# L3DCube_X16_Daughterboard_Rev3.net
KiCad netlist of a schematic drawn in EAGLE
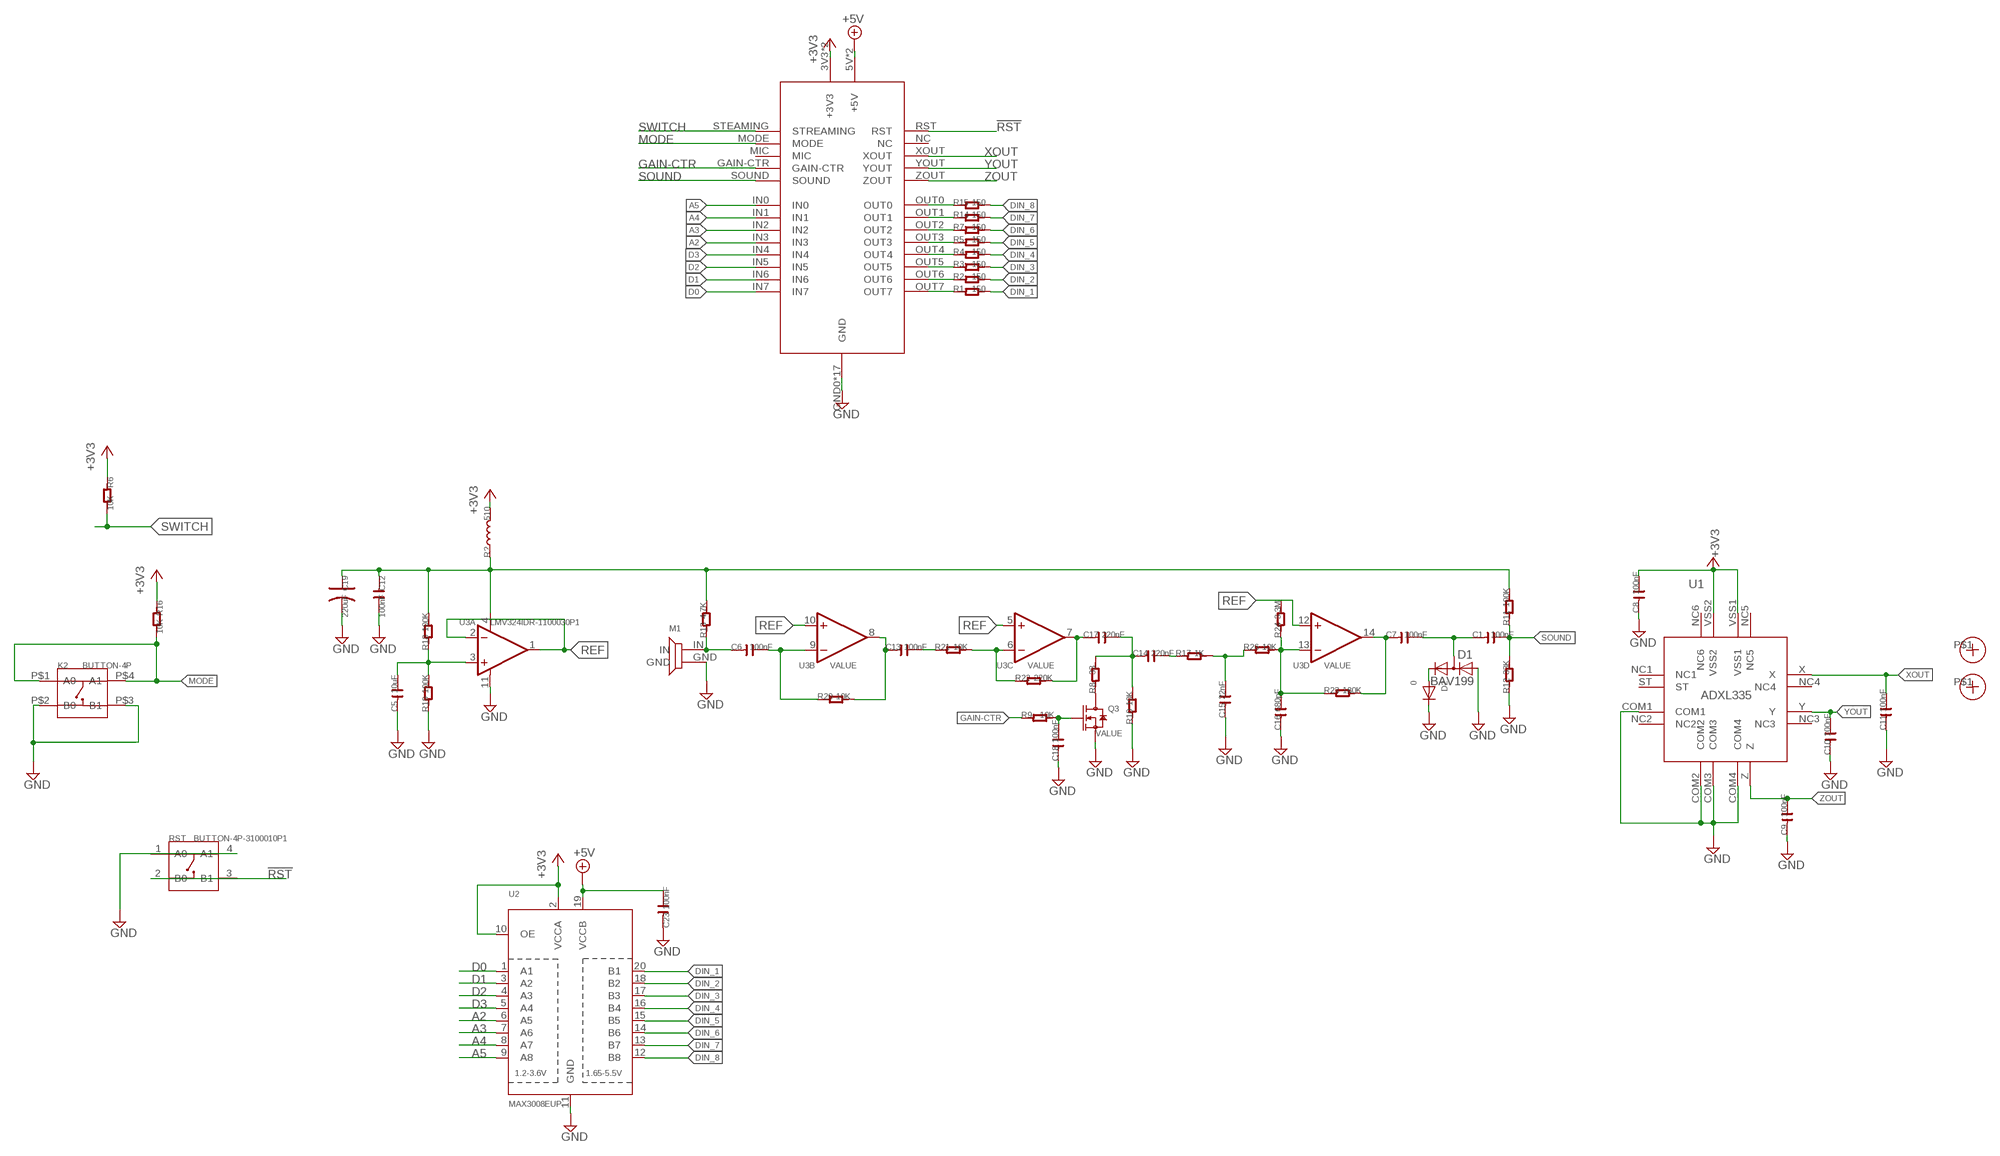
[diagram p0: schematic, sheet 1]

(export (version "E")
  (design (tool "Eeschema 10.0.6"))
  (components
    (comp (ref "C1")
      (value "100nF")
      (footprint "eagle-import:C0603")
      (libsource (lib "eagle-import") (part "C-0603"))
    )
    (comp (ref "C5")
      (value "10uF")
      (footprint "eagle-import:C0603")
      (libsource (lib "eagle-import") (part "C-0603"))
    )
    (comp (ref "C6")
      (value "100nF")
      (footprint "eagle-import:C0603")
      (libsource (lib "eagle-import") (part "C-0603"))
    )
    (comp (ref "C7")
      (value "100nF")
      (footprint "eagle-import:C0603")
      (libsource (lib "eagle-import") (part "C-0603"))
    )
    (comp (ref "C8")
      (value "100nF")
      (footprint "eagle-import:C0603")
      (libsource (lib "eagle-import") (part "C-0603"))
    )
    (comp (ref "C9")
      (value "100nF")
      (footprint "eagle-import:C0603")
      (libsource (lib "eagle-import") (part "C-0603"))
    )
    (comp (ref "C10")
      (value "100nF")
      (footprint "eagle-import:C0603")
      (libsource (lib "eagle-import") (part "C-0603"))
    )
    (comp (ref "C11")
      (value "100nF")
      (footprint "eagle-import:C0603")
      (libsource (lib "eagle-import") (part "C-0603"))
    )
    (comp (ref "C12")
      (value "100nF")
      (footprint "eagle-import:C0603")
      (libsource (lib "eagle-import") (part "C-0603"))
    )
    (comp (ref "C13")
      (value "100nF")
      (footprint "eagle-import:C0603")
      (libsource (lib "eagle-import") (part "C-0603"))
    )
    (comp (ref "C14")
      (value "220nF")
      (footprint "eagle-import:C0603")
      (libsource (lib "eagle-import") (part "C-0603"))
    )
    (comp (ref "C15")
      (value "22nF")
      (footprint "eagle-import:C0603")
      (libsource (lib "eagle-import") (part "C-0603"))
    )
    (comp (ref "C16")
      (value "680pF")
      (footprint "eagle-import:C0603")
      (libsource (lib "eagle-import") (part "C-0603"))
    )
    (comp (ref "C17")
      (value "220nF")
      (footprint "eagle-import:C0603")
      (libsource (lib "eagle-import") (part "C-0603"))
    )
    (comp (ref "C18")
      (value "100nF")
      (footprint "eagle-import:C0603")
      (libsource (lib "eagle-import") (part "C-0603"))
    )
    (comp (ref "C19")
      (value "220uF")
      (footprint "eagle-import:AVX-B")
      (libsource (lib "eagle-import") (part "C-POLAR-B"))
    )
    (comp (ref "C23")
      (value "100nF")
      (footprint "eagle-import:C0603")
      (libsource (lib "eagle-import") (part "C-0603"))
    )
    (comp (ref "D1")
      (value "BAV199")
      (footprint "eagle-import:SOT23")
      (libsource (lib "eagle-import") (part "BAV199"))
    )
    (comp (ref "D2")
      (value "0")
      (footprint "eagle-import:SOD-123")
      (libsource (lib "eagle-import") (part "DIODESOD-123"))
    )
    (comp (ref "K2")
      (value "BUTTON-4P")
      (footprint "eagle-import:4P-12X12X6-SMD")
      (libsource (lib "eagle-import") (part "BUTTON-4P"))
    )
    (comp (ref "M1")
      (value "MICROPHONE")
      (footprint "eagle-import:MICROPHONE")
      (libsource (lib "eagle-import") (part "MICROPHONE"))
    )
    (comp (ref "Q3")
      (value "2N7002")
      (footprint "eagle-import:SOT23")
      (libsource (lib "eagle-import") (part "MOSFET-N-044020001"))
    )
    (comp (ref "R1")
      (value "150")
      (footprint "eagle-import:R0603")
      (libsource (lib "eagle-import") (part "R-0603"))
    )
    (comp (ref "R2")
      (value "150")
      (footprint "eagle-import:R0603")
      (libsource (lib "eagle-import") (part "R-0603"))
    )
    (comp (ref "R3")
      (value "150")
      (footprint "eagle-import:R0603")
      (libsource (lib "eagle-import") (part "R-0603"))
    )
    (comp (ref "R4")
      (value "150")
      (footprint "eagle-import:R0603")
      (libsource (lib "eagle-import") (part "R-0603"))
    )
    (comp (ref "R5")
      (value "150")
      (footprint "eagle-import:R0603")
      (libsource (lib "eagle-import") (part "R-0603"))
    )
    (comp (ref "R6")
      (value "10K")
      (footprint "eagle-import:R0603")
      (libsource (lib "eagle-import") (part "R-0603"))
    )
    (comp (ref "R7")
      (value "150")
      (footprint "eagle-import:R0603")
      (libsource (lib "eagle-import") (part "R-0603"))
    )
    (comp (ref "R8")
      (value "33")
      (footprint "eagle-import:R0603")
      (libsource (lib "eagle-import") (part "R-0603"))
    )
    (comp (ref "R9")
      (value "10K")
      (footprint "eagle-import:R0603")
      (libsource (lib "eagle-import") (part "R-0603"))
    )
    (comp (ref "R10")
      (value "10K")
      (footprint "eagle-import:R0603")
      (libsource (lib "eagle-import") (part "R-0603"))
    )
    (comp (ref "R11")
      (value "100K")
      (footprint "eagle-import:R0603")
      (libsource (lib "eagle-import") (part "R-0603"))
    )
    (comp (ref "R12")
      (value "33K")
      (footprint "eagle-import:R0603")
      (libsource (lib "eagle-import") (part "R-0603"))
    )
    (comp (ref "R13")
      (value "4.7K")
      (footprint "eagle-import:R0603")
      (libsource (lib "eagle-import") (part "R-0603"))
    )
    (comp (ref "R14")
      (value "150")
      (footprint "eagle-import:R0603")
      (libsource (lib "eagle-import") (part "R-0603"))
    )
    (comp (ref "R15")
      (value "150")
      (footprint "eagle-import:R0603")
      (libsource (lib "eagle-import") (part "R-0603"))
    )
    (comp (ref "R16")
      (value "10K")
      (footprint "eagle-import:R0603")
      (libsource (lib "eagle-import") (part "R-0603"))
    )
    (comp (ref "R17")
      (value "1K")
      (footprint "eagle-import:R0603")
      (libsource (lib "eagle-import") (part "R-0603"))
    )
    (comp (ref "R18")
      (value "100K")
      (footprint "eagle-import:R0603")
      (libsource (lib "eagle-import") (part "R-0603"))
    )
    (comp (ref "R19")
      (value "100K")
      (footprint "eagle-import:R0603")
      (libsource (lib "eagle-import") (part "R-0603"))
    )
    (comp (ref "R20")
      (value "10K")
      (footprint "eagle-import:R0603")
      (libsource (lib "eagle-import") (part "R-0603"))
    )
    (comp (ref "R21")
      (value "10K")
      (footprint "eagle-import:R0603")
      (libsource (lib "eagle-import") (part "R-0603"))
    )
    (comp (ref "R22")
      (value "220K")
      (footprint "eagle-import:R0603")
      (libsource (lib "eagle-import") (part "R-0603"))
    )
    (comp (ref "R23")
      (value "180K")
      (footprint "eagle-import:R0603")
      (libsource (lib "eagle-import") (part "R-0603"))
    )
    (comp (ref "R24")
      (value "3.3M")
      (footprint "eagle-import:R0603")
      (libsource (lib "eagle-import") (part "R-0603"))
    )
    (comp (ref "R26")
      (value "10K")
      (footprint "eagle-import:R0603")
      (libsource (lib "eagle-import") (part "R-0603"))
    )
    (comp (ref "R?")
      (value "510")
      (footprint "eagle-import:L0603")
      (libsource (lib "eagle-import") (part "L-0603"))
    )
    (comp (ref "RST")
      (value "BUTTON-4P-3100010P1")
      (footprint "eagle-import:4P-SMD-6.0X6.0X5.0H")
      (libsource (lib "eagle-import") (part "BUTTON-4P-3100010P1"))
    )
    (comp (ref "U$1")
      (value "CUBE-16-DAUGHTERBOARD")
      (footprint "eagle-import:CUBE-16-DAUGHTERBOARD")
      (libsource (lib "eagle-import") (part "CUBE-16-DAUGHTERBOARD"))
    )
    (comp (ref "U$2")
      (value "FIDUCIAL-MARK")
      (footprint "eagle-import:FIDUCIAL-MARK")
      (libsource (lib "eagle-import") (part "FIDUCIAL-MARK"))
    )
    (comp (ref "U$3")
      (value "FIDUCIAL-MARK")
      (footprint "eagle-import:FIDUCIAL-MARK")
      (libsource (lib "eagle-import") (part "FIDUCIAL-MARK"))
    )
    (comp (ref "U1")
      (value "ADXL335")
      (footprint "eagle-import:ADXL335")
      (libsource (lib "eagle-import") (part "ADXL335"))
    )
    (comp (ref "U2")
      (value "MAX3008EUP")
      (footprint "eagle-import:TSSOP20")
      (libsource (lib "eagle-import") (part "TXB0108PWR"))
    )
    (comp (ref "U3")
      (value "LMV324IDR-1100030P1")
      (footprint "eagle-import:SOIC14")
      (libsource (lib "eagle-import") (part "LMV324IDR-1100030P1"))
    )
  )
  (nets
    (net (code "1") (name "+3V3") (class "Default")
      (node (ref "C8") (pin "2") (pinfunction "2_2") (pintype "bidirectional"))
      (node (ref "R16") (pin "1") (pinfunction "1_1") (pintype "bidirectional"))
      (node (ref "R6") (pin "1") (pinfunction "1_1") (pintype "bidirectional"))
      (node (ref "R?") (pin "2") (pinfunction "2_2") (pintype "passive"))
      (node (ref "U$1") (pin "3V3") (pinfunction "+3V3_3V3") (pintype "bidirectional"))
      (node (ref "U$1") (pin "3V3'") (pinfunction "+3V3_3V3'") (pintype "bidirectional"))
      (node (ref "U1") (pin "VSS1") (pinfunction "VSS1_VSS1") (pintype "bidirectional"))
      (node (ref "U1") (pin "VSS2") (pinfunction "VSS2_VSS2") (pintype "bidirectional"))
      (node (ref "U2") (pin "10") (pinfunction "OE_10") (pintype "bidirectional"))
      (node (ref "U2") (pin "2") (pinfunction "VCCA_2") (pintype "bidirectional"))
    )
    (net (code "2") (name "+5V") (class "Default")
      (node (ref "C23") (pin "2") (pinfunction "2_2") (pintype "bidirectional"))
      (node (ref "U$1") (pin "5V") (pinfunction "+5V_5V") (pintype "bidirectional"))
      (node (ref "U$1") (pin "5V'") (pinfunction "+5V_5V'") (pintype "bidirectional"))
      (node (ref "U2") (pin "19") (pinfunction "VCCB_19") (pintype "bidirectional"))
    )
    (net (code "3") (name "/~{RST}") (class "Default")
      (node (ref "RST") (pin "2") (pinfunction "B0_2") (pintype "bidirectional"))
      (node (ref "RST") (pin "3") (pinfunction "B1_3") (pintype "bidirectional"))
      (node (ref "U$1") (pin "RST") (pinfunction "RST_RST") (pintype "bidirectional"))
    )
    (net (code "4") (name "A2") (class "Default")
      (node (ref "U$1") (pin "IN3") (pinfunction "IN3_IN3") (pintype "bidirectional"))
      (node (ref "U2") (pin "6") (pinfunction "A5_6") (pintype "bidirectional"))
    )
    (net (code "5") (name "A3") (class "Default")
      (node (ref "U$1") (pin "IN2") (pinfunction "IN2_IN2") (pintype "bidirectional"))
      (node (ref "U2") (pin "7") (pinfunction "A6_7") (pintype "bidirectional"))
    )
    (net (code "6") (name "A4") (class "Default")
      (node (ref "U$1") (pin "IN1") (pinfunction "IN1_IN1") (pintype "bidirectional"))
      (node (ref "U2") (pin "8") (pinfunction "A7_8") (pintype "bidirectional"))
    )
    (net (code "7") (name "A5") (class "Default")
      (node (ref "U$1") (pin "IN0") (pinfunction "IN0_IN0") (pintype "bidirectional"))
      (node (ref "U2") (pin "9") (pinfunction "A8_9") (pintype "bidirectional"))
    )
    (net (code "8") (name "D0") (class "Default")
      (node (ref "U$1") (pin "IN7") (pinfunction "IN7_IN7") (pintype "bidirectional"))
      (node (ref "U2") (pin "1") (pinfunction "A1_1") (pintype "bidirectional"))
    )
    (net (code "9") (name "D1") (class "Default")
      (node (ref "U$1") (pin "IN6") (pinfunction "IN6_IN6") (pintype "bidirectional"))
      (node (ref "U2") (pin "3") (pinfunction "A2_3") (pintype "bidirectional"))
    )
    (net (code "10") (name "D2") (class "Default")
      (node (ref "U$1") (pin "IN5") (pinfunction "IN5_IN5") (pintype "bidirectional"))
      (node (ref "U2") (pin "4") (pinfunction "A3_4") (pintype "bidirectional"))
    )
    (net (code "11") (name "D3") (class "Default")
      (node (ref "U$1") (pin "IN4") (pinfunction "IN4_IN4") (pintype "bidirectional"))
      (node (ref "U2") (pin "5") (pinfunction "A4_5") (pintype "bidirectional"))
    )
    (net (code "12") (name "DIN_1") (class "Default")
      (node (ref "R1") (pin "2") (pinfunction "2_2") (pintype "bidirectional"))
      (node (ref "U2") (pin "20") (pinfunction "B1_20") (pintype "bidirectional"))
    )
    (net (code "13") (name "DIN_2") (class "Default")
      (node (ref "R2") (pin "2") (pinfunction "2_2") (pintype "bidirectional"))
      (node (ref "U2") (pin "18") (pinfunction "B2_18") (pintype "bidirectional"))
    )
    (net (code "14") (name "DIN_3") (class "Default")
      (node (ref "R3") (pin "2") (pinfunction "2_2") (pintype "bidirectional"))
      (node (ref "U2") (pin "17") (pinfunction "B3_17") (pintype "bidirectional"))
    )
    (net (code "15") (name "DIN_4") (class "Default")
      (node (ref "R4") (pin "2") (pinfunction "2_2") (pintype "bidirectional"))
      (node (ref "U2") (pin "16") (pinfunction "B4_16") (pintype "bidirectional"))
    )
    (net (code "16") (name "DIN_5") (class "Default")
      (node (ref "R5") (pin "2") (pinfunction "2_2") (pintype "bidirectional"))
      (node (ref "U2") (pin "15") (pinfunction "B5_15") (pintype "bidirectional"))
    )
    (net (code "17") (name "DIN_6") (class "Default")
      (node (ref "R7") (pin "2") (pinfunction "2_2") (pintype "bidirectional"))
      (node (ref "U2") (pin "14") (pinfunction "B6_14") (pintype "bidirectional"))
    )
    (net (code "18") (name "DIN_7") (class "Default")
      (node (ref "R14") (pin "2") (pinfunction "2_2") (pintype "bidirectional"))
      (node (ref "U2") (pin "13") (pinfunction "B7_13") (pintype "bidirectional"))
    )
    (net (code "19") (name "DIN_8") (class "Default")
      (node (ref "R15") (pin "2") (pinfunction "2_2") (pintype "bidirectional"))
      (node (ref "U2") (pin "12") (pinfunction "B8_12") (pintype "bidirectional"))
    )
    (net (code "20") (name "GAIN-CTR") (class "Default")
      (node (ref "R9") (pin "1") (pinfunction "1_1") (pintype "bidirectional"))
      (node (ref "U$1") (pin "GAIN-CTR") (pinfunction "GAIN-CTR_GAIN-CTR") (pintype "bidirectional"))
    )
    (net (code "21") (name "GND") (class "Default")
      (node (ref "C10") (pin "1") (pinfunction "1_1") (pintype "bidirectional"))
      (node (ref "C11") (pin "1") (pinfunction "1_1") (pintype "bidirectional"))
      (node (ref "C12") (pin "2") (pinfunction "2_2") (pintype "bidirectional"))
      (node (ref "C15") (pin "1") (pinfunction "1_1") (pintype "bidirectional"))
      (node (ref "C16") (pin "1") (pinfunction "1_1") (pintype "bidirectional"))
      (node (ref "C18") (pin "1") (pinfunction "1_1") (pintype "bidirectional"))
      (node (ref "C19") (pin "-") (pinfunction "2_-") (pintype "bidirectional"))
      (node (ref "C23") (pin "1") (pinfunction "1_1") (pintype "bidirectional"))
      (node (ref "C5") (pin "1") (pinfunction "1_1") (pintype "bidirectional"))
      (node (ref "C8") (pin "1") (pinfunction "1_1") (pintype "bidirectional"))
      (node (ref "C9") (pin "1") (pinfunction "1_1") (pintype "bidirectional"))
      (node (ref "D1") (pin "1") (pinfunction "A_1") (pintype "passive"))
      (node (ref "D2") (pin "C") (pinfunction "C_C") (pintype "passive"))
      (node (ref "K2") (pin "P$2") (pinfunction "B0_P$2") (pintype "bidirectional"))
      (node (ref "K2") (pin "P$3") (pinfunction "B1_P$3") (pintype "bidirectional"))
      (node (ref "M1") (pin "GND") (pinfunction "GND_GND") (pintype "bidirectional"))
      (node (ref "Q3") (pin "2") (pinfunction "S_2") (pintype "passive"))
      (node (ref "R10") (pin "1") (pinfunction "1_1") (pintype "bidirectional"))
      (node (ref "R12") (pin "1") (pinfunction "1_1") (pintype "bidirectional"))
      (node (ref "R19") (pin "1") (pinfunction "1_1") (pintype "bidirectional"))
      (node (ref "RST") (pin "1") (pinfunction "A0_1") (pintype "bidirectional"))
      (node (ref "RST") (pin "4") (pinfunction "A1_4") (pintype "bidirectional"))
      (node (ref "U$1") (pin "GND0") (pinfunction "GND_GND0") (pintype "bidirectional"))
      (node (ref "U$1") (pin "GND1") (pinfunction "GND_GND1") (pintype "bidirectional"))
      (node (ref "U$1") (pin "GND10") (pinfunction "GND_GND10") (pintype "bidirectional"))
      (node (ref "U$1") (pin "GND11") (pinfunction "GND_GND11") (pintype "bidirectional"))
      (node (ref "U$1") (pin "GND13") (pinfunction "GND_GND13") (pintype "bidirectional"))
      (node (ref "U$1") (pin "GND14") (pinfunction "GND_GND14") (pintype "bidirectional"))
      (node (ref "U$1") (pin "GND15") (pinfunction "GND_GND15") (pintype "bidirectional"))
      (node (ref "U$1") (pin "GND16") (pinfunction "GND_GND16") (pintype "bidirectional"))
      (node (ref "U$1") (pin "GND17") (pinfunction "GND_GND17") (pintype "bidirectional"))
      (node (ref "U$1") (pin "GND2") (pinfunction "GND_GND2") (pintype "bidirectional"))
      (node (ref "U$1") (pin "GND3") (pinfunction "GND_GND3") (pintype "bidirectional"))
      (node (ref "U$1") (pin "GND4") (pinfunction "GND_GND4") (pintype "bidirectional"))
      (node (ref "U$1") (pin "GND5") (pinfunction "GND_GND5") (pintype "bidirectional"))
      (node (ref "U$1") (pin "GND7") (pinfunction "GND_GND7") (pintype "bidirectional"))
      (node (ref "U$1") (pin "GND8") (pinfunction "GND_GND8") (pintype "bidirectional"))
      (node (ref "U$1") (pin "GND9") (pinfunction "GND_GND9") (pintype "bidirectional"))
      (node (ref "U$1") (pin "P$37") (pinfunction "GND_P$37") (pintype "bidirectional"))
      (node (ref "U1") (pin "COM1") (pinfunction "COM1_COM1") (pintype "bidirectional"))
      (node (ref "U1") (pin "COM2") (pinfunction "COM2_COM2") (pintype "bidirectional"))
      (node (ref "U1") (pin "COM3") (pinfunction "COM3_COM3") (pintype "bidirectional"))
      (node (ref "U1") (pin "COM4") (pinfunction "COM4_COM4") (pintype "bidirectional"))
      (node (ref "U2") (pin "11") (pinfunction "GND_11") (pintype "bidirectional"))
      (node (ref "U3") (pin "11") (pinfunction "V-_11") (pintype "power_in"))
    )
    (net (code "22") (name "MODE") (class "Default")
      (node (ref "K2") (pin "P$1") (pinfunction "A0_P$1") (pintype "bidirectional"))
      (node (ref "K2") (pin "P$4") (pinfunction "A1_P$4") (pintype "bidirectional"))
      (node (ref "R16") (pin "2") (pinfunction "2_2") (pintype "bidirectional"))
      (node (ref "U$1") (pin "MODE") (pinfunction "MODE_MODE") (pintype "bidirectional"))
    )
    (net (code "23") (name "Net-(C6-Pad1)") (class "Default")
      (node (ref "C6") (pin "1") (pinfunction "1_1") (pintype "bidirectional"))
      (node (ref "M1") (pin "IN") (pinfunction "IN_IN") (pintype "bidirectional"))
      (node (ref "R13") (pin "1") (pinfunction "1_1") (pintype "bidirectional"))
    )
    (net (code "24") (name "Net-(C13-Pad2)") (class "Default")
      (node (ref "C13") (pin "2") (pinfunction "2_2") (pintype "bidirectional"))
      (node (ref "R21") (pin "1") (pinfunction "1_1") (pintype "bidirectional"))
    )
    (net (code "25") (name "Net-(C14-Pad1)") (class "Default")
      (node (ref "C14") (pin "1") (pinfunction "1_1") (pintype "bidirectional"))
      (node (ref "C17") (pin "2") (pinfunction "2_2") (pintype "bidirectional"))
      (node (ref "R10") (pin "2") (pinfunction "2_2") (pintype "bidirectional"))
      (node (ref "R8") (pin "2") (pinfunction "2_2") (pintype "bidirectional"))
    )
    (net (code "26") (name "Net-(C14-Pad2)") (class "Default")
      (node (ref "C14") (pin "2") (pinfunction "2_2") (pintype "bidirectional"))
      (node (ref "R17") (pin "1") (pinfunction "1_1") (pintype "bidirectional"))
    )
    (net (code "27") (name "Net-(C15-Pad2)") (class "Default")
      (node (ref "C15") (pin "2") (pinfunction "2_2") (pintype "bidirectional"))
      (node (ref "R17") (pin "2") (pinfunction "2_2") (pintype "bidirectional"))
      (node (ref "R26") (pin "1") (pinfunction "1_1") (pintype "bidirectional"))
    )
    (net (code "28") (name "Net-(C19-1)") (class "Default")
      (node (ref "C12") (pin "1") (pinfunction "1_1") (pintype "bidirectional"))
      (node (ref "C19") (pin "+") (pinfunction "1_+") (pintype "bidirectional"))
      (node (ref "R11") (pin "2") (pinfunction "2_2") (pintype "bidirectional"))
      (node (ref "R13") (pin "2") (pinfunction "2_2") (pintype "bidirectional"))
      (node (ref "R18") (pin "2") (pinfunction "2_2") (pintype "bidirectional"))
      (node (ref "R?") (pin "1") (pinfunction "1_1") (pintype "passive"))
      (node (ref "U3") (pin "4") (pinfunction "V+_4") (pintype "power_in"))
    )
    (net (code "29") (name "Net-(D1-AC)") (class "Default")
      (node (ref "C1") (pin "1") (pinfunction "1_1") (pintype "bidirectional"))
      (node (ref "C7") (pin "2") (pinfunction "2_2") (pintype "bidirectional"))
      (node (ref "D1") (pin "3") (pinfunction "AC_3") (pintype "passive"))
    )
    (net (code "30") (name "Net-(D1-C)") (class "Default")
      (node (ref "D1") (pin "2") (pinfunction "C_2") (pintype "passive"))
      (node (ref "D2") (pin "A") (pinfunction "A_A") (pintype "passive"))
    )
    (net (code "31") (name "Net-(Q3-D)") (class "Default")
      (node (ref "Q3") (pin "3") (pinfunction "D_3") (pintype "passive"))
      (node (ref "R8") (pin "1") (pinfunction "1_1") (pintype "bidirectional"))
    )
    (net (code "32") (name "Net-(Q3-G)") (class "Default")
      (node (ref "C18") (pin "2") (pinfunction "2_2") (pintype "bidirectional"))
      (node (ref "Q3") (pin "1") (pinfunction "G_1") (pintype "passive"))
      (node (ref "R9") (pin "2") (pinfunction "2_2") (pintype "bidirectional"))
    )
    (net (code "33") (name "Net-(R1-Pad1)") (class "Default")
      (node (ref "R1") (pin "1") (pinfunction "1_1") (pintype "bidirectional"))
      (node (ref "U$1") (pin "OUT7") (pinfunction "OUT7_OUT7") (pintype "bidirectional"))
    )
    (net (code "34") (name "Net-(R2-Pad1)") (class "Default")
      (node (ref "R2") (pin "1") (pinfunction "1_1") (pintype "bidirectional"))
      (node (ref "U$1") (pin "OUT6") (pinfunction "OUT6_OUT6") (pintype "bidirectional"))
    )
    (net (code "35") (name "Net-(R3-Pad1)") (class "Default")
      (node (ref "R3") (pin "1") (pinfunction "1_1") (pintype "bidirectional"))
      (node (ref "U$1") (pin "OUT5") (pinfunction "OUT5_OUT5") (pintype "bidirectional"))
    )
    (net (code "36") (name "Net-(R4-Pad1)") (class "Default")
      (node (ref "R4") (pin "1") (pinfunction "1_1") (pintype "bidirectional"))
      (node (ref "U$1") (pin "OUT4") (pinfunction "OUT4_OUT4") (pintype "bidirectional"))
    )
    (net (code "37") (name "Net-(R5-Pad1)") (class "Default")
      (node (ref "R5") (pin "1") (pinfunction "1_1") (pintype "bidirectional"))
      (node (ref "U$1") (pin "OUT3") (pinfunction "OUT3_OUT3") (pintype "bidirectional"))
    )
    (net (code "38") (name "Net-(R7-Pad1)") (class "Default")
      (node (ref "R7") (pin "1") (pinfunction "1_1") (pintype "bidirectional"))
      (node (ref "U$1") (pin "OUT2") (pinfunction "OUT2_OUT2") (pintype "bidirectional"))
    )
    (net (code "39") (name "Net-(R14-Pad1)") (class "Default")
      (node (ref "R14") (pin "1") (pinfunction "1_1") (pintype "bidirectional"))
      (node (ref "U$1") (pin "OUT1") (pinfunction "OUT1_OUT1") (pintype "bidirectional"))
    )
    (net (code "40") (name "Net-(R15-Pad1)") (class "Default")
      (node (ref "R15") (pin "1") (pinfunction "1_1") (pintype "bidirectional"))
      (node (ref "U$1") (pin "OUT0") (pinfunction "OUT0_OUT0") (pintype "bidirectional"))
    )
    (net (code "41") (name "Net-(U3A-IN+)") (class "Default")
      (node (ref "C5") (pin "2") (pinfunction "2_2") (pintype "bidirectional"))
      (node (ref "R18") (pin "1") (pinfunction "1_1") (pintype "bidirectional"))
      (node (ref "R19") (pin "2") (pinfunction "2_2") (pintype "bidirectional"))
      (node (ref "U3") (pin "3") (pinfunction "IN+_3") (pintype "input"))
    )
    (net (code "42") (name "Net-(U3B-IN-)") (class "Default")
      (node (ref "C6") (pin "2") (pinfunction "2_2") (pintype "bidirectional"))
      (node (ref "R20") (pin "1") (pinfunction "1_1") (pintype "bidirectional"))
      (node (ref "U3") (pin "9") (pinfunction "IN-_9") (pintype "input"))
    )
    (net (code "43") (name "Net-(U3B-OUT)") (class "Default")
      (node (ref "C13") (pin "1") (pinfunction "1_1") (pintype "bidirectional"))
      (node (ref "R20") (pin "2") (pinfunction "2_2") (pintype "bidirectional"))
      (node (ref "U3") (pin "8") (pinfunction "OUT_8") (pintype "output"))
    )
    (net (code "44") (name "Net-(U3C-IN-)") (class "Default")
      (node (ref "R21") (pin "2") (pinfunction "2_2") (pintype "bidirectional"))
      (node (ref "R22") (pin "1") (pinfunction "1_1") (pintype "bidirectional"))
      (node (ref "U3") (pin "6") (pinfunction "IN-_6") (pintype "input"))
    )
    (net (code "45") (name "Net-(U3C-OUT)") (class "Default")
      (node (ref "C17") (pin "1") (pinfunction "1_1") (pintype "bidirectional"))
      (node (ref "R22") (pin "2") (pinfunction "2_2") (pintype "bidirectional"))
      (node (ref "U3") (pin "7") (pinfunction "OUT_7") (pintype "output"))
    )
    (net (code "46") (name "Net-(U3D-IN-)") (class "Default")
      (node (ref "C16") (pin "2") (pinfunction "2_2") (pintype "bidirectional"))
      (node (ref "R23") (pin "1") (pinfunction "1_1") (pintype "bidirectional"))
      (node (ref "R24") (pin "1") (pinfunction "1_1") (pintype "bidirectional"))
      (node (ref "R26") (pin "2") (pinfunction "2_2") (pintype "bidirectional"))
      (node (ref "U3") (pin "13") (pinfunction "IN-_13") (pintype "input"))
    )
    (net (code "47") (name "Net-(U3D-OUT)") (class "Default")
      (node (ref "C7") (pin "1") (pinfunction "1_1") (pintype "bidirectional"))
      (node (ref "R23") (pin "2") (pinfunction "2_2") (pintype "bidirectional"))
      (node (ref "U3") (pin "14") (pinfunction "OUT_14") (pintype "output"))
    )
    (net (code "48") (name "REF") (class "Default")
      (node (ref "R24") (pin "2") (pinfunction "2_2") (pintype "bidirectional"))
      (node (ref "U3") (pin "1") (pinfunction "OUT_1") (pintype "output"))
      (node (ref "U3") (pin "10") (pinfunction "IN+_10") (pintype "input"))
      (node (ref "U3") (pin "12") (pinfunction "IN+_12") (pintype "input"))
      (node (ref "U3") (pin "2") (pinfunction "IN-_2") (pintype "input"))
      (node (ref "U3") (pin "5") (pinfunction "IN+_5") (pintype "input"))
    )
    (net (code "49") (name "SOUND") (class "Default")
      (node (ref "C1") (pin "2") (pinfunction "2_2") (pintype "bidirectional"))
      (node (ref "R11") (pin "1") (pinfunction "1_1") (pintype "bidirectional"))
      (node (ref "R12") (pin "2") (pinfunction "2_2") (pintype "bidirectional"))
      (node (ref "U$1") (pin "SOUND") (pinfunction "SOUND_SOUND") (pintype "bidirectional"))
    )
    (net (code "50") (name "SWITCH") (class "Default")
      (node (ref "R6") (pin "2") (pinfunction "2_2") (pintype "bidirectional"))
      (node (ref "U$1") (pin "STEAMING") (pinfunction "STREAMING_STEAMING") (pintype "bidirectional"))
    )
    (net (code "51") (name "XOUT") (class "Default")
      (node (ref "C11") (pin "2") (pinfunction "2_2") (pintype "bidirectional"))
      (node (ref "U$1") (pin "XOUT") (pinfunction "XOUT_XOUT") (pintype "bidirectional"))
      (node (ref "U1") (pin "X") (pinfunction "X_X") (pintype "bidirectional"))
    )
    (net (code "52") (name "YOUT") (class "Default")
      (node (ref "C10") (pin "2") (pinfunction "2_2") (pintype "bidirectional"))
      (node (ref "U$1") (pin "YOUT") (pinfunction "YOUT_YOUT") (pintype "bidirectional"))
      (node (ref "U1") (pin "Y") (pinfunction "Y_Y") (pintype "bidirectional"))
    )
    (net (code "53") (name "ZOUT") (class "Default")
      (node (ref "C9") (pin "2") (pinfunction "2_2") (pintype "bidirectional"))
      (node (ref "U$1") (pin "ZOUT") (pinfunction "ZOUT_ZOUT") (pintype "bidirectional"))
      (node (ref "U1") (pin "Z") (pinfunction "Z_Z") (pintype "bidirectional"))
    )
    (net (code "54") (name "unconnected-(U$1-PadMIC)") (class "Default")
      (node (ref "U$1") (pin "MIC") (pinfunction "MIC_MIC") (pintype "bidirectional"))
    )
    (net (code "55") (name "unconnected-(U$1-PadNC)") (class "Default")
      (node (ref "U$1") (pin "NC") (pinfunction "NC_NC") (pintype "bidirectional"))
    )
    (net (code "56") (name "unconnected-(U$2-PadP$1)") (class "Default")
      (node (ref "U$2") (pin "P$1") (pinfunction "P$1_P$1") (pintype "bidirectional"))
    )
    (net (code "57") (name "unconnected-(U$3-PadP$1)") (class "Default")
      (node (ref "U$3") (pin "P$1") (pinfunction "P$1_P$1") (pintype "bidirectional"))
    )
    (net (code "58") (name "unconnected-(U1-PadNC1)") (class "Default")
      (node (ref "U1") (pin "NC1") (pinfunction "NC1_NC1") (pintype "bidirectional"))
    )
    (net (code "59") (name "unconnected-(U1-PadNC2)") (class "Default")
      (node (ref "U1") (pin "NC2") (pinfunction "NC2_NC2") (pintype "bidirectional"))
    )
    (net (code "60") (name "unconnected-(U1-PadNC3)") (class "Default")
      (node (ref "U1") (pin "NC3") (pinfunction "NC3_NC3") (pintype "bidirectional"))
    )
    (net (code "61") (name "unconnected-(U1-PadNC4)") (class "Default")
      (node (ref "U1") (pin "NC4") (pinfunction "NC4_NC4") (pintype "bidirectional"))
    )
    (net (code "62") (name "unconnected-(U1-PadNC5)") (class "Default")
      (node (ref "U1") (pin "NC5") (pinfunction "NC5_NC5") (pintype "bidirectional"))
    )
    (net (code "63") (name "unconnected-(U1-PadNC6)") (class "Default")
      (node (ref "U1") (pin "NC6") (pinfunction "NC6_NC6") (pintype "bidirectional"))
    )
    (net (code "64") (name "unconnected-(U1-PadST)") (class "Default")
      (node (ref "U1") (pin "ST") (pinfunction "ST_ST") (pintype "bidirectional"))
    )
  )
)
